# sch.net
KiCad netlist of a schematic drawn in EasyEDA
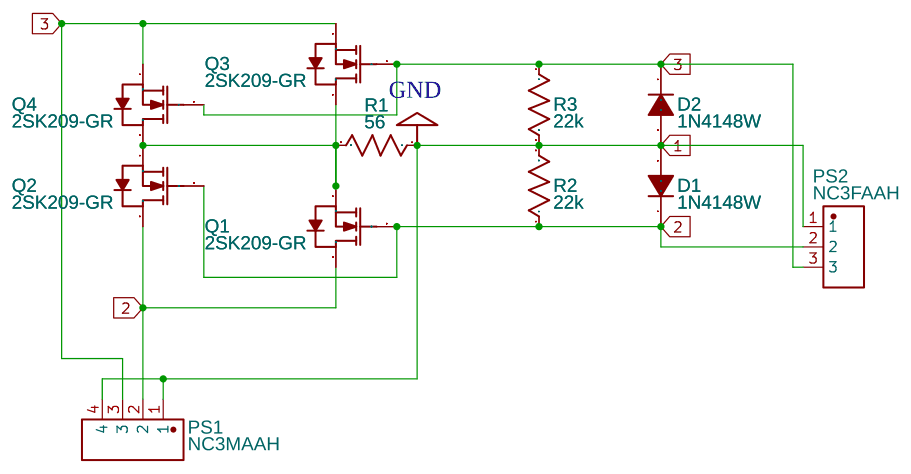
[diagram p0: schematic sheet]

(export (version "E")
  (design (tool "Eeschema 10.0.6"))
  (components
    (comp (ref "D1")
      (value "1N4148W")
      (fields (field (name "Manufacturer") "MDD"))
      (libsource (lib "") (part "1N4148W-C84367_1"))
    )
    (comp (ref "D2")
      (value "1N4148W")
      (fields (field (name "Manufacturer") "MDD"))
      (libsource (lib "") (part "1N4148W-C84367"))
    )
    (comp (ref "PS1")
      (value "NC3MAAH")
      (fields (field (name "Manufacturer") "Neutrik"))
      (libsource (lib "") (part "NC3MAAH"))
    )
    (comp (ref "PS2")
      (value "NC3FAAH")
      (fields (field (name "Manufacturer") "Neutrik"))
      (libsource (lib "") (part "NC3FAAH"))
    )
    (comp (ref "Q1")
      (value "2SK209-GR")
      (fields (field (name "Manufacturer Part") "2SK209-GR(TE85L,F)") (field (name "Manufacturer") "TOSHIBA"))
      (libsource (lib "") (part "2SK209-GR(TE85L,F)"))
    )
    (comp (ref "Q2")
      (value "2SK209-GR")
      (fields (field (name "Manufacturer Part") "2SK209-GR(TE85L,F)") (field (name "Manufacturer") "TOSHIBA"))
      (libsource (lib "") (part "2SK209-GR(TE85L,F)"))
    )
    (comp (ref "Q3")
      (value "2SK209-GR")
      (fields (field (name "Manufacturer Part") "2SK209-GR(TE85L,F)") (field (name "Manufacturer") "TOSHIBA"))
      (libsource (lib "") (part "2SK209-GR(TE85L,F)"))
    )
    (comp (ref "Q4")
      (value "2SK209-GR")
      (fields (field (name "Manufacturer Part") "2SK209-GR(TE85L,F)") (field (name "Manufacturer") "TOSHIBA"))
      (libsource (lib "") (part "2SK209-GR(TE85L,F)"))
    )
    (comp (ref "R1") (value "56") (libsource (lib "") (part "R_0805_US")))
    (comp (ref "R2") (value "22k") (libsource (lib "") (part "R_0805_US_2")))
    (comp (ref "R3") (value "22k") (libsource (lib "") (part "R_0805_US_1")))
  )
  (nets
    (net (code "1") (name "1") (class "Default")
      (node (ref "D1") (pin "2") (pinfunction "A_2") (pintype "unspecified"))
      (node (ref "D2") (pin "2") (pinfunction "A_2") (pintype "unspecified"))
      (node (ref "PS1") (pin "1") (pinfunction "1_1") (pintype "unspecified"))
      (node (ref "PS1") (pin "4") (pinfunction "4_4") (pintype "unspecified"))
      (node (ref "PS2") (pin "1") (pinfunction "1_1") (pintype "unspecified"))
      (node (ref "R1") (pin "1") (pinfunction "1_1") (pintype "unspecified"))
      (node (ref "R2") (pin "2") (pinfunction "2_2") (pintype "unspecified"))
      (node (ref "R3") (pin "2") (pinfunction "2_2") (pintype "unspecified"))
    )
    (net (code "2") (name "2") (class "Default")
      (node (ref "D1") (pin "1") (pinfunction "C_1") (pintype "unspecified"))
      (node (ref "PS1") (pin "2") (pinfunction "2_2") (pintype "unspecified"))
      (node (ref "PS2") (pin "2") (pinfunction "2_2") (pintype "unspecified"))
      (node (ref "Q1") (pin "2") (pinfunction "D_2") (pintype "unspecified"))
      (node (ref "Q1") (pin "3") (pinfunction "G_3") (pintype "unspecified"))
      (node (ref "Q2") (pin "2") (pinfunction "D_2") (pintype "unspecified"))
      (node (ref "Q2") (pin "3") (pinfunction "G_3") (pintype "unspecified"))
      (node (ref "R2") (pin "1") (pinfunction "1_1") (pintype "unspecified"))
    )
    (net (code "3") (name "3") (class "Default")
      (node (ref "D2") (pin "1") (pinfunction "C_1") (pintype "unspecified"))
      (node (ref "PS1") (pin "3") (pinfunction "3_3") (pintype "unspecified"))
      (node (ref "PS2") (pin "3") (pinfunction "3_3") (pintype "unspecified"))
      (node (ref "Q3") (pin "1") (pinfunction "S_1") (pintype "unspecified"))
      (node (ref "Q3") (pin "3") (pinfunction "G_3") (pintype "unspecified"))
      (node (ref "Q4") (pin "1") (pinfunction "S_1") (pintype "unspecified"))
      (node (ref "Q4") (pin "3") (pinfunction "G_3") (pintype "unspecified"))
      (node (ref "R3") (pin "1") (pinfunction "1_1") (pintype "unspecified"))
    )
    (net (code "4") (name "Net-(Q1-S)") (class "Default")
      (node (ref "Q1") (pin "1") (pinfunction "S_1") (pintype "unspecified"))
      (node (ref "Q2") (pin "1") (pinfunction "S_1") (pintype "unspecified"))
      (node (ref "Q3") (pin "2") (pinfunction "D_2") (pintype "unspecified"))
      (node (ref "Q4") (pin "2") (pinfunction "D_2") (pintype "unspecified"))
      (node (ref "R1") (pin "2") (pinfunction "2_2") (pintype "unspecified"))
    )
  )
)
